# schluecki.net
KiCad netlist of a schematic drawn in EAGLE
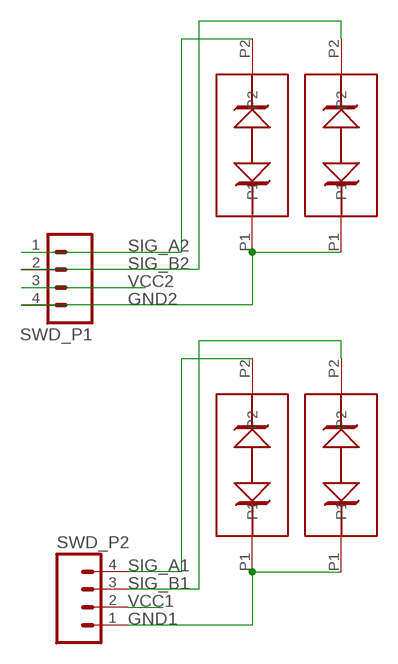
[diagram p0: schematic, sheet 1]

(export (version "E")
  (design (tool "Eeschema 10.0.6"))
  (components
    (comp (ref "SWD_P1")
      (value "M04")
      (footprint "eagle-import:04P")
      (libsource (lib "eagle-import") (part "M04"))
    )
    (comp (ref "SWD_P2")
      (value "M04")
      (footprint "eagle-import:04P")
      (libsource (lib "eagle-import") (part "M04"))
    )
    (comp (ref "U$1")
      (value "SMB/DO-214AA")
      (footprint "eagle-import:DO-214AA")
      (libsource (lib "eagle-import") (part "SMB/DO-214AA"))
    )
    (comp (ref "U$2")
      (value "SMB/DO-214AA")
      (footprint "eagle-import:DO-214AA")
      (libsource (lib "eagle-import") (part "SMB/DO-214AA"))
    )
    (comp (ref "U$3")
      (value "SMB/DO-214AA")
      (footprint "eagle-import:DO-214AA")
      (libsource (lib "eagle-import") (part "SMB/DO-214AA"))
    )
    (comp (ref "U$4")
      (value "SMB/DO-214AA")
      (footprint "eagle-import:DO-214AA")
      (libsource (lib "eagle-import") (part "SMB/DO-214AA"))
    )
  )
  (nets
    (net (code "1") (name "/GND1") (class "Default")
      (node (ref "SWD_P2") (pin "1") (pinfunction "1_1") (pintype "passive"))
      (node (ref "U$1") (pin "P1") (pinfunction "P1_P1") (pintype "bidirectional"))
      (node (ref "U$2") (pin "P1") (pinfunction "P1_P1") (pintype "bidirectional"))
    )
    (net (code "2") (name "/GND2") (class "Default")
      (node (ref "SWD_P1") (pin "4") (pinfunction "4_4") (pintype "passive"))
      (node (ref "U$3") (pin "P1") (pinfunction "P1_P1") (pintype "bidirectional"))
      (node (ref "U$4") (pin "P1") (pinfunction "P1_P1") (pintype "bidirectional"))
    )
    (net (code "3") (name "/SIG_A1") (class "Default")
      (node (ref "SWD_P2") (pin "4") (pinfunction "4_4") (pintype "passive"))
      (node (ref "U$1") (pin "P2") (pinfunction "P2_P2") (pintype "bidirectional"))
    )
    (net (code "4") (name "/SIG_A2") (class "Default")
      (node (ref "SWD_P1") (pin "1") (pinfunction "1_1") (pintype "passive"))
      (node (ref "U$3") (pin "P2") (pinfunction "P2_P2") (pintype "bidirectional"))
    )
    (net (code "5") (name "/SIG_B1") (class "Default")
      (node (ref "SWD_P2") (pin "3") (pinfunction "3_3") (pintype "passive"))
      (node (ref "U$2") (pin "P2") (pinfunction "P2_P2") (pintype "bidirectional"))
    )
    (net (code "6") (name "/SIG_B2") (class "Default")
      (node (ref "SWD_P1") (pin "2") (pinfunction "2_2") (pintype "passive"))
      (node (ref "U$4") (pin "P2") (pinfunction "P2_P2") (pintype "bidirectional"))
    )
    (net (code "7") (name "/VCC1") (class "Default")
      (node (ref "SWD_P2") (pin "2") (pinfunction "2_2") (pintype "passive"))
    )
    (net (code "8") (name "/VCC2") (class "Default")
      (node (ref "SWD_P1") (pin "3") (pinfunction "3_3") (pintype "passive"))
    )
  )
)
